# Pg04__AM335X_Section_3.net
KiCad netlist of a schematic drawn in Altium Designer
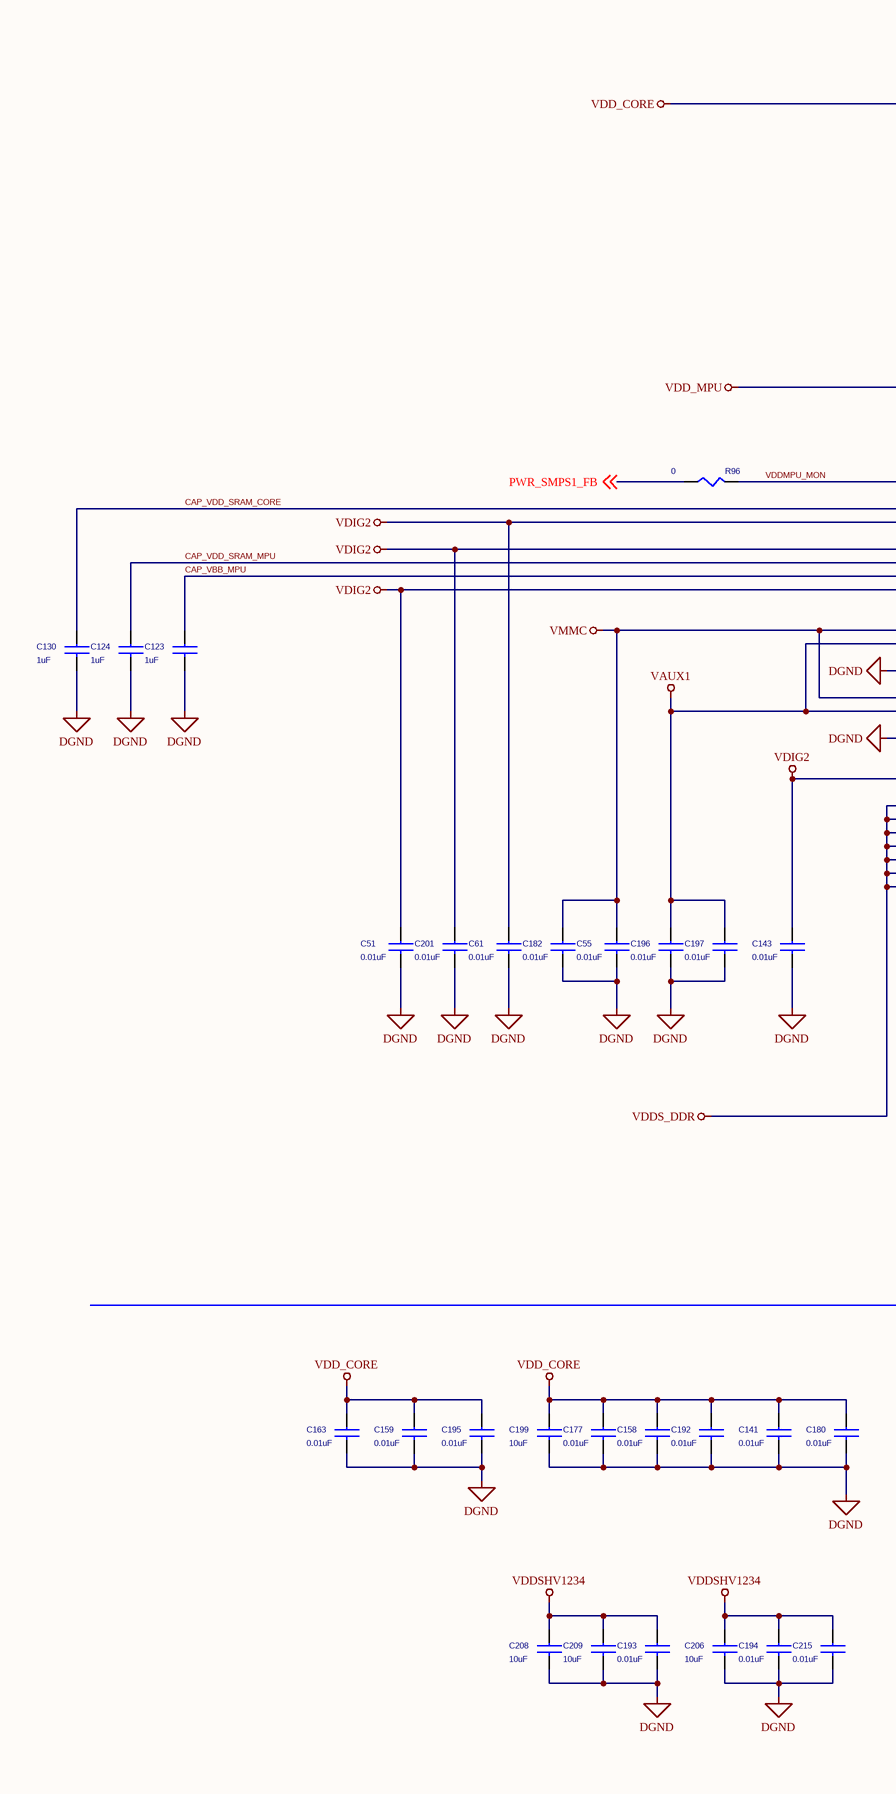
[diagram p0: Pg04_ AM335X Section 3 .SchDoc, left]
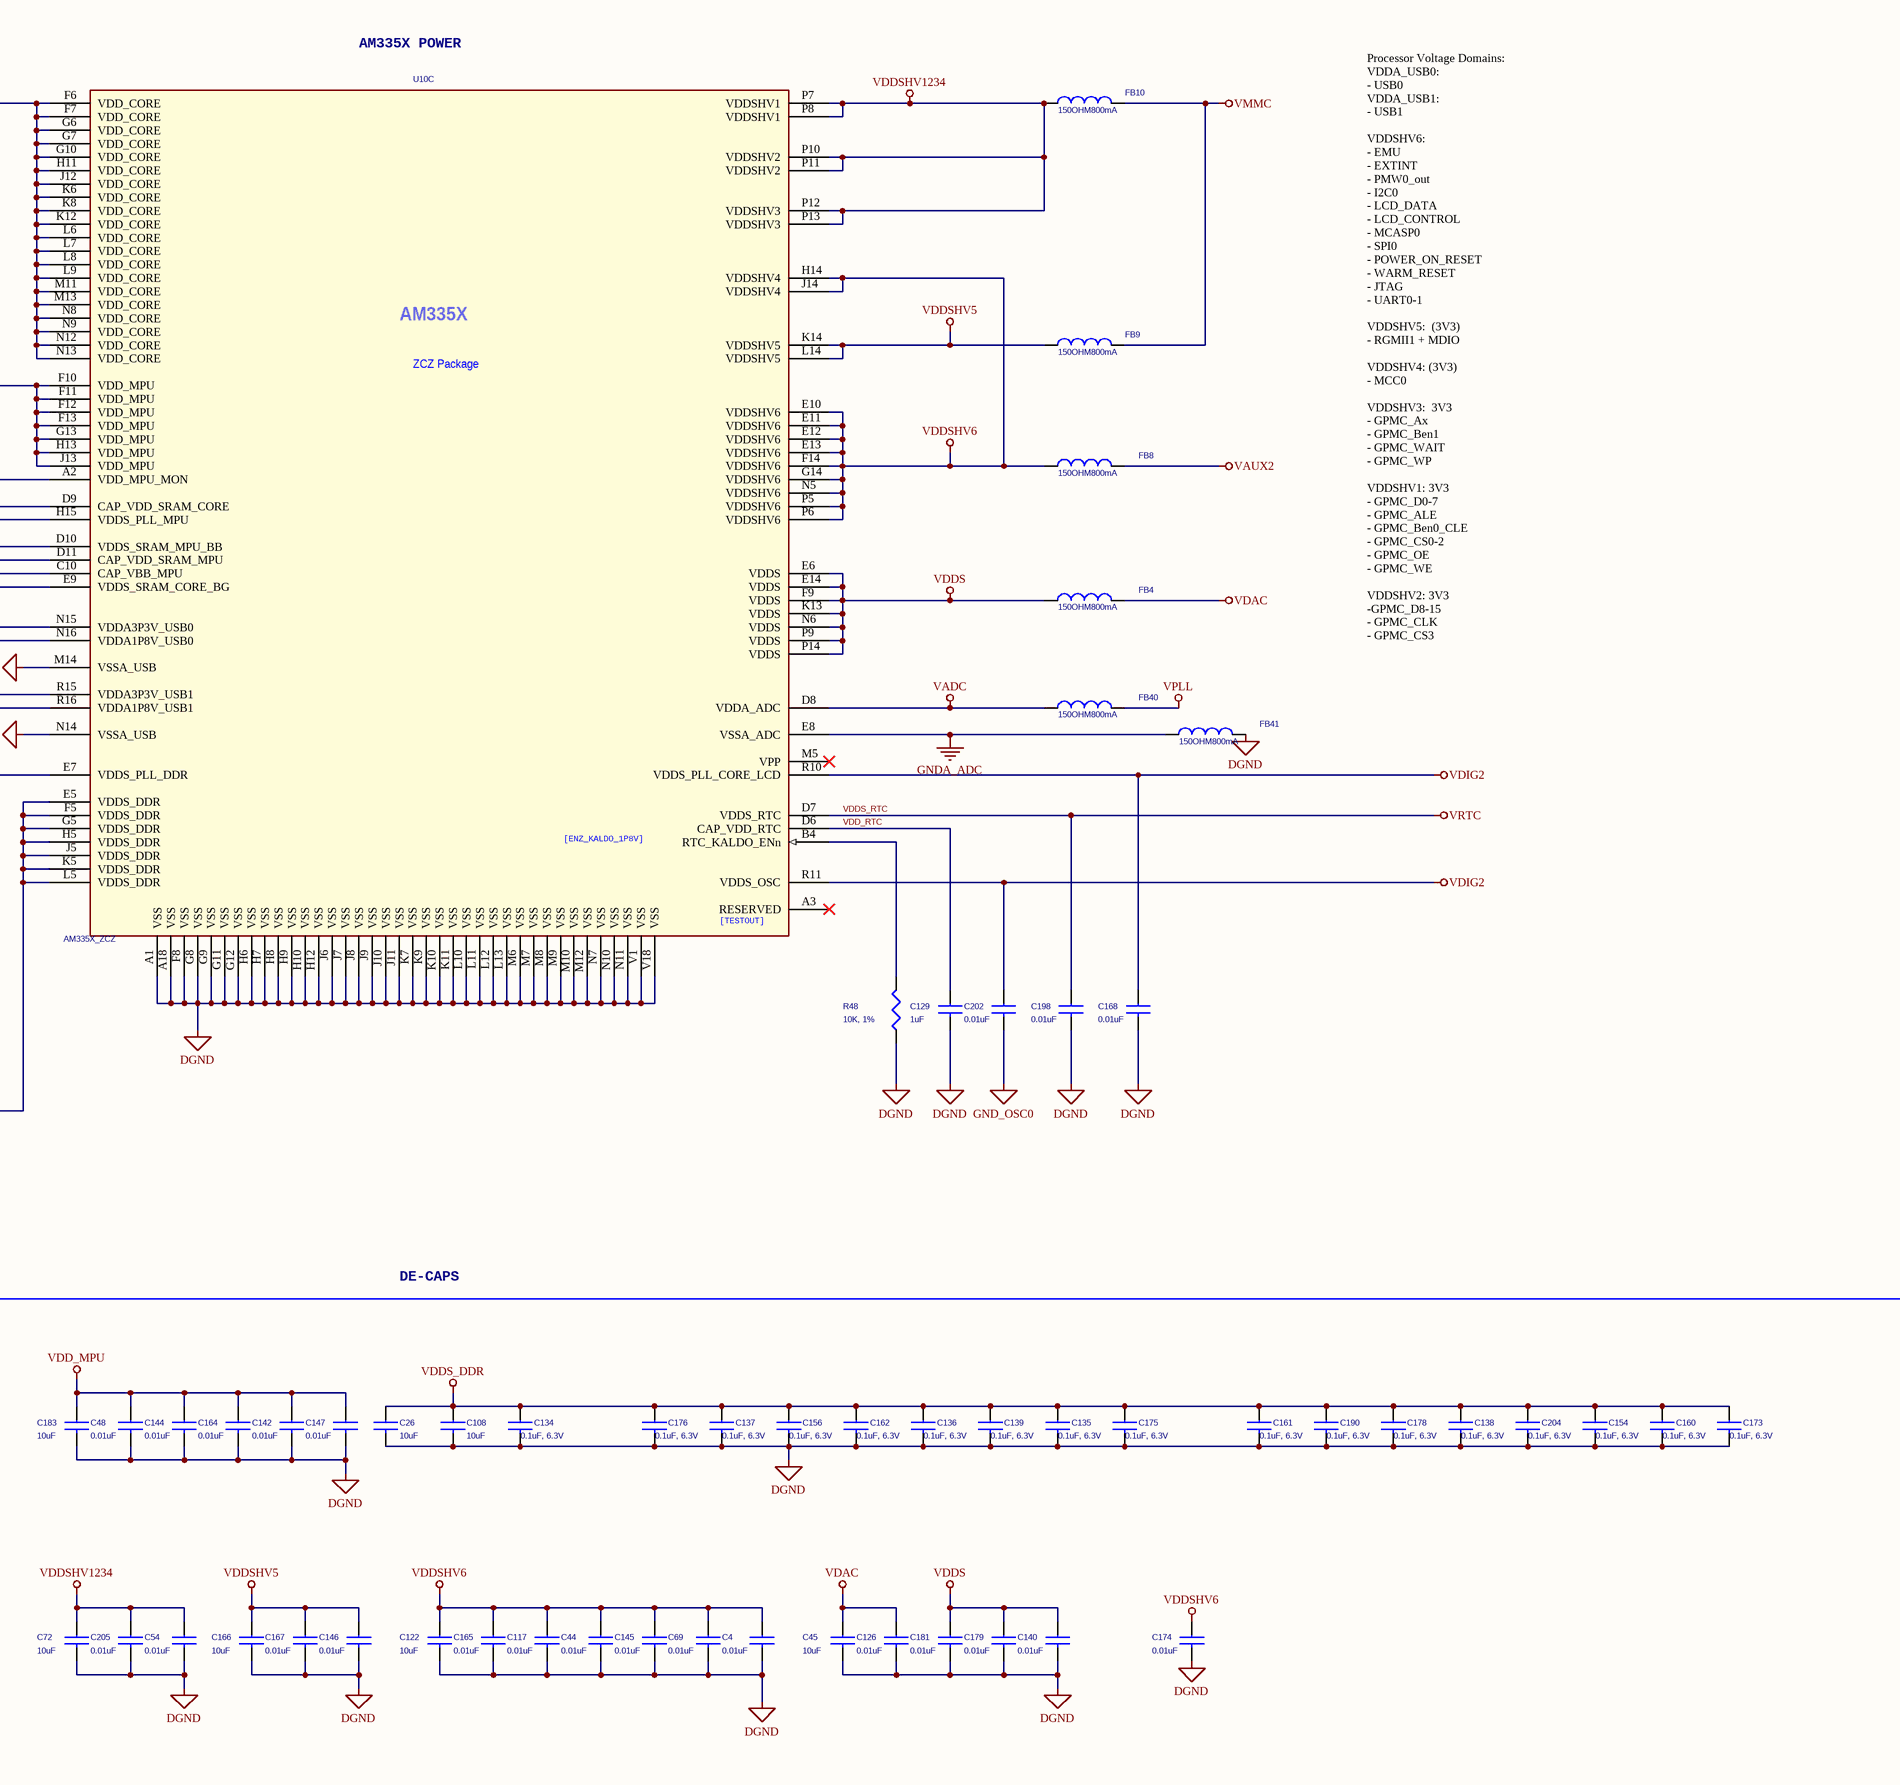
[diagram p1: Pg04_ AM335X Section 3 .SchDoc, right]

(export (version "E")
  (design (tool "Eeschema 10.0.6"))
  (components
    (comp (ref "C4")
      (value "0.01uF")
      (footprint "SM-7351-CAP-0402")
      (fields (field (name "MFR") "Panasonic") (field (name "TIINTPARTNUMBER") "1C0012"))
      (libsource (lib "*") (part "0.01uFCapacitor16V10%0402_Dup1"))
    )
    (comp (ref "C26")
      (value "10uF")
      (footprint "SM-7351-CAP-0805")
      (description "Capacitor 10uF 16V 10% Ceramic 0805")
      (fields (field (name "MFR") "AVX") (field (name "TIINTPARTNUMBER") "1C0085"))
      (libsource (lib "*") (part "10uFCapacitor16V10%0805"))
    )
    (comp (ref "C44")
      (value "0.01uF")
      (footprint "SM-7351-CAP-0402")
      (fields (field (name "MFR") "Panasonic") (field (name "TIINTPARTNUMBER") "1C0012"))
      (libsource (lib "*") (part "0.01uFCapacitor16V10%0402_Dup1"))
    )
    (comp (ref "C45")
      (value "10uF")
      (footprint "SM-7351-CAP-0805")
      (description "Capacitor 10uF 16V 10% Ceramic 0805")
      (fields (field (name "MFR") "AVX") (field (name "TIINTPARTNUMBER") "1C0085"))
      (libsource (lib "*") (part "10uFCapacitor16V10%0805"))
    )
    (comp (ref "C48")
      (value "0.01uF")
      (footprint "SM-7351-CAP-0402")
      (fields (field (name "MFR") "Panasonic") (field (name "TIINTPARTNUMBER") "1C0012"))
      (libsource (lib "*") (part "0.01uFCapacitor16V10%0402_Dup1"))
    )
    (comp (ref "C51")
      (value "0.01uF")
      (footprint "SM-7351-CAP-0402")
      (fields (field (name "MFR") "Panasonic") (field (name "TIINTPARTNUMBER") "1C0012"))
      (libsource (lib "*") (part "0.01uFCapacitor16V10%0402_Dup1"))
    )
    (comp (ref "C54")
      (value "0.01uF")
      (footprint "SM-7351-CAP-0402")
      (fields (field (name "MFR") "Panasonic") (field (name "TIINTPARTNUMBER") "1C0012"))
      (libsource (lib "*") (part "0.01uFCapacitor16V10%0402_Dup1"))
    )
    (comp (ref "C55")
      (value "0.01uF")
      (footprint "SM-7351-CAP-0402")
      (fields (field (name "MFR") "Panasonic") (field (name "TIINTPARTNUMBER") "1C0012"))
      (libsource (lib "*") (part "0.01uFCapacitor16V10%0402_Dup1"))
    )
    (comp (ref "C61")
      (value "0.01uF")
      (footprint "SM-7351-CAP-0402")
      (fields (field (name "MFR") "Panasonic") (field (name "TIINTPARTNUMBER") "1C0012"))
      (libsource (lib "*") (part "0.01uFCapacitor16V10%0402_Dup1"))
    )
    (comp (ref "C69")
      (value "0.01uF")
      (footprint "SM-7351-CAP-0402")
      (fields (field (name "MFR") "Panasonic") (field (name "TIINTPARTNUMBER") "1C0012"))
      (libsource (lib "*") (part "0.01uFCapacitor16V10%0402_Dup1"))
    )
    (comp (ref "C72")
      (value "10uF")
      (footprint "SM-7351-CAP-0805")
      (description "Capacitor 10uF 16V 10% Ceramic 0805")
      (fields (field (name "MFR") "AVX") (field (name "TIINTPARTNUMBER") "1C0085"))
      (libsource (lib "*") (part "10uFCapacitor16V10%0805"))
    )
    (comp (ref "C108")
      (value "10uF")
      (footprint "SM-7351-CAP-0805")
      (description "Capacitor 10uF 16V 10% Ceramic 0805")
      (fields (field (name "MFR") "AVX") (field (name "TIINTPARTNUMBER") "1C0085"))
      (libsource (lib "*") (part "10uFCapacitor16V10%0805"))
    )
    (comp (ref "C117")
      (value "0.01uF")
      (footprint "SM-7351-CAP-0402")
      (fields (field (name "MFR") "Panasonic") (field (name "TIINTPARTNUMBER") "1C0012"))
      (libsource (lib "*") (part "0.01uFCapacitor16V10%0402_Dup1"))
    )
    (comp (ref "C122")
      (value "10uF")
      (footprint "SM-7351-CAP-0805")
      (description "Capacitor 10uF 16V 10% Ceramic 0805")
      (fields (field (name "MFR") "AVX") (field (name "TIINTPARTNUMBER") "1C0085"))
      (libsource (lib "*") (part "10uFCapacitor16V10%0805"))
    )
    (comp (ref "C123")
      (value "1uF")
      (footprint "SM-7351-CAP-0402")
      (fields (field (name "MFR") "AVX") (field (name "TIINTPARTNUMBER") "1C0084"))
      (libsource (lib "*") (part "1uFCapacitor10V10%0402_Dup1"))
    )
    (comp (ref "C124")
      (value "1uF")
      (footprint "SM-7351-CAP-0402")
      (fields (field (name "MFR") "AVX") (field (name "TIINTPARTNUMBER") "1C0084"))
      (libsource (lib "*") (part "1uFCapacitor10V10%0402_Dup1"))
    )
    (comp (ref "C126")
      (value "0.01uF")
      (footprint "SM-7351-CAP-0402")
      (fields (field (name "MFR") "Panasonic") (field (name "TIINTPARTNUMBER") "1C0012"))
      (libsource (lib "*") (part "0.01uFCapacitor16V10%0402_Dup1"))
    )
    (comp (ref "C129")
      (value "1uF")
      (footprint "SM-7351-CAP-0402")
      (fields (field (name "MFR") "AVX") (field (name "TIINTPARTNUMBER") "1C0084"))
      (libsource (lib "*") (part "1uFCapacitor10V10%0402_Dup1"))
    )
    (comp (ref "C130")
      (value "1uF")
      (footprint "SM-7351-CAP-0402")
      (fields (field (name "MFR") "AVX") (field (name "TIINTPARTNUMBER") "1C0084"))
      (libsource (lib "*") (part "1uFCapacitor10V10%0402_Dup1"))
    )
    (comp (ref "C134")
      (value "0.1uF, 6.3V")
      (footprint "SM-7351-CAP-0402")
      (fields (field (name "MFR") "Murata") (field (name "TIINTPARTNUMBER") "1C0122"))
      (libsource (lib "*") (part "0.1uFCapacitor6.3V10%0201"))
    )
    (comp (ref "C135")
      (value "0.1uF, 6.3V")
      (footprint "SM-7351-CAP-0402")
      (fields (field (name "MFR") "Murata") (field (name "TIINTPARTNUMBER") "1C0122"))
      (libsource (lib "*") (part "0.1uFCapacitor6.3V10%0201"))
    )
    (comp (ref "C136")
      (value "0.1uF, 6.3V")
      (footprint "SM-7351-CAP-0402")
      (fields (field (name "MFR") "Murata") (field (name "TIINTPARTNUMBER") "1C0122"))
      (libsource (lib "*") (part "0.1uFCapacitor6.3V10%0201"))
    )
    (comp (ref "C137")
      (value "0.1uF, 6.3V")
      (footprint "SMD0201")
      (fields (field (name "MFR") "Murata") (field (name "TIINTPARTNUMBER") "1C0122"))
      (libsource (lib "*") (part "0.1uFCapacitor6.3V10%0201"))
    )
    (comp (ref "C138")
      (value "0.1uF, 6.3V")
      (footprint "SMD0201")
      (fields (field (name "MFR") "Murata") (field (name "TIINTPARTNUMBER") "1C0122"))
      (libsource (lib "*") (part "0.1uFCapacitor6.3V10%0201"))
    )
    (comp (ref "C139")
      (value "0.1uF, 6.3V")
      (footprint "SMD0201")
      (fields (field (name "MFR") "Murata") (field (name "TIINTPARTNUMBER") "1C0122"))
      (libsource (lib "*") (part "0.1uFCapacitor6.3V10%0201"))
    )
    (comp (ref "C140")
      (value "0.01uF")
      (footprint "SM-7351-CAP-0402")
      (fields (field (name "MFR") "Panasonic") (field (name "TIINTPARTNUMBER") "1C0012"))
      (libsource (lib "*") (part "0.01uFCapacitor16V10%0402_Dup1"))
    )
    (comp (ref "C141")
      (value "0.01uF")
      (footprint "SM-7351-CAP-0402")
      (fields (field (name "MFR") "Panasonic") (field (name "TIINTPARTNUMBER") "1C0012"))
      (libsource (lib "*") (part "0.01uFCapacitor16V10%0402_Dup1"))
    )
    (comp (ref "C142")
      (value "0.01uF")
      (footprint "SM-7351-CAP-0402")
      (fields (field (name "MFR") "Panasonic") (field (name "TIINTPARTNUMBER") "1C0012"))
      (libsource (lib "*") (part "0.01uFCapacitor16V10%0402_Dup1"))
    )
    (comp (ref "C143")
      (value "0.01uF")
      (footprint "SM-7351-CAP-0402")
      (fields (field (name "MFR") "Panasonic") (field (name "TIINTPARTNUMBER") "1C0012"))
      (libsource (lib "*") (part "0.01uFCapacitor16V10%0402_Dup1"))
    )
    (comp (ref "C144")
      (value "0.01uF")
      (footprint "SM-7351-CAP-0402")
      (fields (field (name "MFR") "Panasonic") (field (name "TIINTPARTNUMBER") "1C0012"))
      (libsource (lib "*") (part "0.01uFCapacitor16V10%0402_Dup1"))
    )
    (comp (ref "C145")
      (value "0.01uF")
      (footprint "SM-7351-CAP-0402")
      (fields (field (name "MFR") "Panasonic") (field (name "TIINTPARTNUMBER") "1C0012"))
      (libsource (lib "*") (part "0.01uFCapacitor16V10%0402_Dup1"))
    )
    (comp (ref "C146")
      (value "0.01uF")
      (footprint "SM-7351-CAP-0402")
      (fields (field (name "MFR") "Panasonic") (field (name "TIINTPARTNUMBER") "1C0012"))
      (libsource (lib "*") (part "0.01uFCapacitor16V10%0402_Dup1"))
    )
    (comp (ref "C147")
      (value "0.01uF")
      (footprint "SM-7351-CAP-0402")
      (fields (field (name "MFR") "Panasonic") (field (name "TIINTPARTNUMBER") "1C0012"))
      (libsource (lib "*") (part "0.01uFCapacitor16V10%0402_Dup1"))
    )
    (comp (ref "C154")
      (value "0.1uF, 6.3V")
      (footprint "SMD0201")
      (fields (field (name "MFR") "Murata") (field (name "TIINTPARTNUMBER") "1C0122"))
      (libsource (lib "*") (part "0.1uFCapacitor6.3V10%0201"))
    )
    (comp (ref "C156")
      (value "0.1uF, 6.3V")
      (footprint "SMD0201")
      (fields (field (name "MFR") "Murata") (field (name "TIINTPARTNUMBER") "1C0122"))
      (libsource (lib "*") (part "0.1uFCapacitor6.3V10%0201"))
    )
    (comp (ref "C158")
      (value "0.01uF")
      (footprint "SM-7351-CAP-0402")
      (fields (field (name "MFR") "Panasonic") (field (name "TIINTPARTNUMBER") "1C0012"))
      (libsource (lib "*") (part "0.01uFCapacitor16V10%0402_Dup1"))
    )
    (comp (ref "C159")
      (value "0.01uF")
      (footprint "SM-7351-CAP-0402")
      (fields (field (name "MFR") "Panasonic") (field (name "TIINTPARTNUMBER") "1C0012"))
      (libsource (lib "*") (part "0.01uFCapacitor16V10%0402_Dup1"))
    )
    (comp (ref "C160")
      (value "0.1uF, 6.3V")
      (footprint "SMD0201")
      (fields (field (name "MFR") "Murata") (field (name "TIINTPARTNUMBER") "1C0122"))
      (libsource (lib "*") (part "0.1uFCapacitor6.3V10%0201"))
    )
    (comp (ref "C161")
      (value "0.1uF, 6.3V")
      (footprint "SMD0201")
      (fields (field (name "MFR") "Murata") (field (name "TIINTPARTNUMBER") "1C0122"))
      (libsource (lib "*") (part "0.1uFCapacitor6.3V10%0201"))
    )
    (comp (ref "C162")
      (value "0.1uF, 6.3V")
      (footprint "SMD0201")
      (fields (field (name "MFR") "Murata") (field (name "TIINTPARTNUMBER") "1C0122"))
      (libsource (lib "*") (part "0.1uFCapacitor6.3V10%0201"))
    )
    (comp (ref "C163")
      (value "0.01uF")
      (footprint "SM-7351-CAP-0402")
      (fields (field (name "MFR") "Panasonic") (field (name "TIINTPARTNUMBER") "1C0012"))
      (libsource (lib "*") (part "0.01uFCapacitor16V10%0402_Dup1"))
    )
    (comp (ref "C164")
      (value "0.01uF")
      (footprint "SM-7351-CAP-0402")
      (fields (field (name "MFR") "Panasonic") (field (name "TIINTPARTNUMBER") "1C0012"))
      (libsource (lib "*") (part "0.01uFCapacitor16V10%0402_Dup1"))
    )
    (comp (ref "C165")
      (value "0.01uF")
      (footprint "SM-7351-CAP-0402")
      (fields (field (name "MFR") "Panasonic") (field (name "TIINTPARTNUMBER") "1C0012"))
      (libsource (lib "*") (part "0.01uFCapacitor16V10%0402_Dup1"))
    )
    (comp (ref "C166")
      (value "10uF")
      (footprint "SM-7351-CAP-0805")
      (description "Capacitor 10uF 16V 10% Ceramic 0805")
      (fields (field (name "MFR") "AVX") (field (name "TIINTPARTNUMBER") "1C0085"))
      (libsource (lib "*") (part "10uFCapacitor16V10%0805"))
    )
    (comp (ref "C167")
      (value "0.01uF")
      (footprint "SM-7351-CAP-0402")
      (fields (field (name "MFR") "Panasonic") (field (name "TIINTPARTNUMBER") "1C0012"))
      (libsource (lib "*") (part "0.01uFCapacitor16V10%0402_Dup1"))
    )
    (comp (ref "C168")
      (value "0.01uF")
      (footprint "SM-7351-CAP-0402")
      (fields (field (name "MFR") "Panasonic") (field (name "TIINTPARTNUMBER") "1C0012"))
      (libsource (lib "*") (part "0.01uFCapacitor16V10%0402_Dup1"))
    )
    (comp (ref "C173")
      (value "0.1uF, 6.3V")
      (footprint "SMD0201")
      (fields (field (name "MFR") "Murata") (field (name "TIINTPARTNUMBER") "1C0122"))
      (libsource (lib "*") (part "0.1uFCapacitor6.3V10%0201"))
    )
    (comp (ref "C174")
      (value "0.01uF")
      (footprint "SM-7351-CAP-0402")
      (fields (field (name "MFR") "Panasonic") (field (name "TIINTPARTNUMBER") "1C0012"))
      (libsource (lib "*") (part "0.01uFCapacitor16V10%0402_Dup1"))
    )
    (comp (ref "C175")
      (value "0.1uF, 6.3V")
      (footprint "SMD0201")
      (fields (field (name "MFR") "Murata") (field (name "TIINTPARTNUMBER") "1C0122"))
      (libsource (lib "*") (part "0.1uFCapacitor6.3V10%0201"))
    )
    (comp (ref "C176")
      (value "0.1uF, 6.3V")
      (footprint "SMD0201")
      (fields (field (name "MFR") "Murata") (field (name "TIINTPARTNUMBER") "1C0122"))
      (libsource (lib "*") (part "0.1uFCapacitor6.3V10%0201"))
    )
    (comp (ref "C177")
      (value "0.01uF")
      (footprint "SM-7351-CAP-0402")
      (fields (field (name "MFR") "Panasonic") (field (name "TIINTPARTNUMBER") "1C0012"))
      (libsource (lib "*") (part "0.01uFCapacitor16V10%0402_Dup1"))
    )
    (comp (ref "C178")
      (value "0.1uF, 6.3V")
      (footprint "SMD0201")
      (fields (field (name "MFR") "Murata") (field (name "TIINTPARTNUMBER") "1C0122"))
      (libsource (lib "*") (part "0.1uFCapacitor6.3V10%0201"))
    )
    (comp (ref "C179")
      (value "0.01uF")
      (footprint "SM-7351-CAP-0402")
      (fields (field (name "MFR") "Panasonic") (field (name "TIINTPARTNUMBER") "1C0012"))
      (libsource (lib "*") (part "0.01uFCapacitor16V10%0402_Dup1"))
    )
    (comp (ref "C180")
      (value "0.01uF")
      (footprint "SM-7351-CAP-0402")
      (fields (field (name "MFR") "Panasonic") (field (name "TIINTPARTNUMBER") "1C0012"))
      (libsource (lib "*") (part "0.01uFCapacitor16V10%0402_Dup1"))
    )
    (comp (ref "C181")
      (value "0.01uF")
      (footprint "SM-7351-CAP-0402")
      (fields (field (name "MFR") "Panasonic") (field (name "TIINTPARTNUMBER") "1C0012"))
      (libsource (lib "*") (part "0.01uFCapacitor16V10%0402_Dup1"))
    )
    (comp (ref "C182")
      (value "0.01uF")
      (footprint "SM-7351-CAP-0402")
      (fields (field (name "MFR") "Panasonic") (field (name "TIINTPARTNUMBER") "1C0012"))
      (libsource (lib "*") (part "0.01uFCapacitor16V10%0402_Dup1"))
    )
    (comp (ref "C183")
      (value "10uF")
      (footprint "SM-7351-CAP-0805")
      (description "Capacitor 10uF 16V 10% Ceramic 0805")
      (fields (field (name "MFR") "AVX") (field (name "TIINTPARTNUMBER") "1C0085"))
      (libsource (lib "*") (part "10uFCapacitor16V10%0805"))
    )
    (comp (ref "C190")
      (value "0.1uF, 6.3V")
      (footprint "SM-7351-CAP-0402")
      (fields (field (name "MFR") "Murata") (field (name "TIINTPARTNUMBER") "1C0122"))
      (libsource (lib "*") (part "0.1uFCapacitor6.3V10%0201"))
    )
    (comp (ref "C192")
      (value "0.01uF")
      (footprint "SM-7351-CAP-0402")
      (fields (field (name "MFR") "Panasonic") (field (name "TIINTPARTNUMBER") "1C0012"))
      (libsource (lib "*") (part "0.01uFCapacitor16V10%0402_Dup1"))
    )
    (comp (ref "C193")
      (value "0.01uF")
      (footprint "SM-7351-CAP-0402")
      (fields (field (name "MFR") "Panasonic") (field (name "TIINTPARTNUMBER") "1C0012"))
      (libsource (lib "*") (part "0.01uFCapacitor16V10%0402_Dup1"))
    )
    (comp (ref "C194")
      (value "0.01uF")
      (footprint "SM-7351-CAP-0402")
      (fields (field (name "MFR") "Panasonic") (field (name "TIINTPARTNUMBER") "1C0012"))
      (libsource (lib "*") (part "0.01uFCapacitor16V10%0402_Dup1"))
    )
    (comp (ref "C195")
      (value "0.01uF")
      (footprint "SM-7351-CAP-0402")
      (fields (field (name "MFR") "Panasonic") (field (name "TIINTPARTNUMBER") "1C0012"))
      (libsource (lib "*") (part "0.01uFCapacitor16V10%0402_Dup1"))
    )
    (comp (ref "C196")
      (value "0.01uF")
      (footprint "SM-7351-CAP-0402")
      (fields (field (name "MFR") "Panasonic") (field (name "TIINTPARTNUMBER") "1C0012"))
      (libsource (lib "*") (part "0.01uFCapacitor16V10%0402_Dup1"))
    )
    (comp (ref "C197")
      (value "0.01uF")
      (footprint "SM-7351-CAP-0402")
      (fields (field (name "MFR") "Panasonic") (field (name "TIINTPARTNUMBER") "1C0012"))
      (libsource (lib "*") (part "0.01uFCapacitor16V10%0402_Dup1"))
    )
    (comp (ref "C198")
      (value "0.01uF")
      (footprint "SM-7351-CAP-0402")
      (fields (field (name "MFR") "Panasonic") (field (name "TIINTPARTNUMBER") "1C0012"))
      (libsource (lib "*") (part "0.01uFCapacitor16V10%0402_Dup1"))
    )
    (comp (ref "C199")
      (value "10uF")
      (footprint "SM-7351-CAP-0805")
      (description "Capacitor 10uF 16V 10% Ceramic 0805")
      (fields (field (name "MFR") "AVX") (field (name "TIINTPARTNUMBER") "1C0085"))
      (libsource (lib "*") (part "10uFCapacitor16V10%0805"))
    )
    (comp (ref "C201")
      (value "0.01uF")
      (footprint "SM-7351-CAP-0402")
      (fields (field (name "MFR") "Panasonic") (field (name "TIINTPARTNUMBER") "1C0012"))
      (libsource (lib "*") (part "0.01uFCapacitor16V10%0402_Dup1"))
    )
    (comp (ref "C202")
      (value "0.01uF")
      (footprint "SM-7351-CAP-0402")
      (fields (field (name "MFR") "Panasonic") (field (name "TIINTPARTNUMBER") "1C0012"))
      (libsource (lib "*") (part "0.01uFCapacitor16V10%0402_Dup1"))
    )
    (comp (ref "C204")
      (value "0.1uF, 6.3V")
      (footprint "SM-7351-CAP-0402")
      (fields (field (name "MFR") "Murata") (field (name "TIINTPARTNUMBER") "1C0122"))
      (libsource (lib "*") (part "0.1uFCapacitor6.3V10%0201"))
    )
    (comp (ref "C205")
      (value "0.01uF")
      (footprint "SM-7351-CAP-0402")
      (fields (field (name "MFR") "Panasonic") (field (name "TIINTPARTNUMBER") "1C0012"))
      (libsource (lib "*") (part "0.01uFCapacitor16V10%0402_Dup1"))
    )
    (comp (ref "C206")
      (value "10uF")
      (footprint "SM-7351-CAP-0805")
      (description "Capacitor 10uF 16V 10% Ceramic 0805")
      (fields (field (name "MFR") "AVX") (field (name "TIINTPARTNUMBER") "1C0085"))
      (libsource (lib "*") (part "10uFCapacitor16V10%0805"))
    )
    (comp (ref "C208")
      (value "10uF")
      (footprint "SM-7351-CAP-0805")
      (description "Capacitor 10uF 16V 10% Ceramic 0805")
      (fields (field (name "MFR") "AVX") (field (name "TIINTPARTNUMBER") "1C0085"))
      (libsource (lib "*") (part "10uFCapacitor16V10%0805"))
    )
    (comp (ref "C209")
      (value "10uF")
      (footprint "SM-7351-CAP-0805")
      (description "Capacitor 10uF 16V 10% Ceramic 0805")
      (fields (field (name "MFR") "AVX") (field (name "TIINTPARTNUMBER") "1C0085"))
      (libsource (lib "*") (part "10uFCapacitor16V10%0805"))
    )
    (comp (ref "C215")
      (value "0.01uF")
      (footprint "SM-7351-CAP-0402")
      (fields (field (name "MFR") "Panasonic") (field (name "TIINTPARTNUMBER") "1C0012"))
      (libsource (lib "*") (part "0.01uFCapacitor16V10%0402_Dup1"))
    )
    (comp (ref "FB4")
      (value "150OHM800mA")
      (footprint "sm-7351-ind-0805")
      (description "Ferrite Bead 150 Ohm 800mA")
      (fields (field (name "MFR") "Steward") (field (name "TIINTPARTNUMBER") "1L0010"))
      (libsource (lib "*") (part "FerBead_12"))
    )
    (comp (ref "FB8")
      (value "150OHM800mA")
      (footprint "sm-7351-ind-0805")
      (description "Ferrite Bead 150 Ohm 800mA")
      (fields (field (name "MFR") "Steward") (field (name "TIINTPARTNUMBER") "1L0010"))
      (libsource (lib "*") (part "FerBead_12"))
    )
    (comp (ref "FB9")
      (value "150OHM800mA")
      (footprint "sm-7351-ind-0805")
      (description "Ferrite Bead 150 Ohm 800mA")
      (fields (field (name "MFR") "Steward") (field (name "TIINTPARTNUMBER") "1L0010"))
      (libsource (lib "*") (part "FerBead_11"))
    )
    (comp (ref "FB10")
      (value "150OHM800mA")
      (footprint "sm-7351-ind-0805")
      (description "Ferrite Bead 150 Ohm 800mA")
      (fields (field (name "MFR") "Steward") (field (name "TIINTPARTNUMBER") "1L0010"))
      (libsource (lib "*") (part "FerBead_7"))
    )
    (comp (ref "FB40")
      (value "150OHM800mA")
      (footprint "sm-7351-ind-0805")
      (description "Ferrite Bead 150 Ohm 800mA")
      (fields (field (name "MFR") "Steward") (field (name "TIINTPARTNUMBER") "1L0010"))
      (libsource (lib "*") (part "FerBead_12"))
    )
    (comp (ref "FB41")
      (value "150OHM800mA")
      (footprint "sm-7351-ind-0805")
      (description "Ferrite Bead 150 Ohm 800mA")
      (fields (field (name "MFR") "Steward") (field (name "TIINTPARTNUMBER") "1L0010"))
      (libsource (lib "*") (part "FerBead_12"))
    )
    (comp (ref "R48")
      (value "10K, 1%")
      (footprint "SM-7351-RES-0402")
      (fields (field (name "TIINTPARTNUMBER") "1R0254") (field (name "MFR") "PANASONIC-ECG"))
      (libsource (lib "*") (part "10KOhmResistor1/10W1%0402_Dup2"))
    )
    (comp (ref "R96")
      (value "0")
      (footprint "SM-7351-RES-0402")
      (description "Resistor Zero ohm Jumper 0402")
      (fields (field (name "TIINTPARTNUMBER") "1R0098") (field (name "MFR") "Panasonic"))
      (libsource (lib "*") (part "ZeroOhmResistor1/16W0402_Dup4"))
    )
    (comp (ref "U10")
      (value "AM335X_ZCZ")
      (footprint "BGA15X15-324-55M")
      (fields (field (name "TIINTPARTNUMBER") "1A0242") (field (name "MFR") "TI"))
      (libsource (lib "*") (part "AM335X_15mmx15mm"))
    )
  )
  (nets
    (net (code "1") (name "/CAP_VBB_MPU") (class "Default")
      (node (ref "C123") (pin "1") (pinfunction "1_1") (pintype "passive"))
      (node (ref "U10") (pin "C10") (pinfunction "CAP_VBB_MPU_C10") (pintype "passive"))
    )
    (net (code "2") (name "/CAP_VDD_SRAM_CORE") (class "Default")
      (node (ref "C130") (pin "1") (pinfunction "1_1") (pintype "passive"))
      (node (ref "U10") (pin "D9") (pinfunction "CAP_VDD_SRAM_CORE_D9") (pintype "power_in"))
    )
    (net (code "3") (name "/CAP_VDD_SRAM_MPU") (class "Default")
      (node (ref "C124") (pin "1") (pinfunction "1_1") (pintype "passive"))
      (node (ref "U10") (pin "D11") (pinfunction "CAP_VDD_SRAM_MPU_D11") (pintype "power_in"))
    )
    (net (code "4") (name "/VDDMPU_MON") (class "Default")
      (node (ref "R96") (pin "1") (pinfunction "P1_1") (pintype "passive"))
      (node (ref "U10") (pin "A2") (pinfunction "VDD_MPU_MON_A2") (pintype "passive"))
    )
    (net (code "5") (name "/VDD_RTC") (class "Default")
      (node (ref "C129") (pin "1") (pinfunction "1_1") (pintype "passive"))
      (node (ref "U10") (pin "D6") (pinfunction "CAP_VDD_RTC_D6") (pintype "power_in"))
    )
    (net (code "6") (name "DGND") (class "Default")
      (node (ref "C108") (pin "2") (pinfunction "2_2") (pintype "passive"))
      (node (ref "C117") (pin "2") (pinfunction "2_2") (pintype "passive"))
      (node (ref "C122") (pin "2") (pinfunction "2_2") (pintype "passive"))
      (node (ref "C123") (pin "2") (pinfunction "2_2") (pintype "passive"))
      (node (ref "C124") (pin "2") (pinfunction "2_2") (pintype "passive"))
      (node (ref "C126") (pin "2") (pinfunction "2_2") (pintype "passive"))
      (node (ref "C129") (pin "2") (pinfunction "2_2") (pintype "passive"))
      (node (ref "C130") (pin "2") (pinfunction "2_2") (pintype "passive"))
      (node (ref "C134") (pin "2") (pinfunction "2_2") (pintype "passive"))
      (node (ref "C135") (pin "2") (pinfunction "2_2") (pintype "passive"))
      (node (ref "C136") (pin "2") (pinfunction "2_2") (pintype "passive"))
      (node (ref "C137") (pin "2") (pinfunction "2_2") (pintype "passive"))
      (node (ref "C138") (pin "2") (pinfunction "2_2") (pintype "passive"))
      (node (ref "C139") (pin "2") (pinfunction "2_2") (pintype "passive"))
      (node (ref "C140") (pin "2") (pinfunction "2_2") (pintype "passive"))
      (node (ref "C141") (pin "2") (pinfunction "2_2") (pintype "passive"))
      (node (ref "C142") (pin "2") (pinfunction "2_2") (pintype "passive"))
      (node (ref "C143") (pin "2") (pinfunction "2_2") (pintype "passive"))
      (node (ref "C144") (pin "2") (pinfunction "2_2") (pintype "passive"))
      (node (ref "C145") (pin "2") (pinfunction "2_2") (pintype "passive"))
      (node (ref "C146") (pin "2") (pinfunction "2_2") (pintype "passive"))
      (node (ref "C147") (pin "2") (pinfunction "2_2") (pintype "passive"))
      (node (ref "C154") (pin "2") (pinfunction "2_2") (pintype "passive"))
      (node (ref "C156") (pin "2") (pinfunction "2_2") (pintype "passive"))
      (node (ref "C158") (pin "2") (pinfunction "2_2") (pintype "passive"))
      (node (ref "C159") (pin "2") (pinfunction "2_2") (pintype "passive"))
      (node (ref "C160") (pin "2") (pinfunction "2_2") (pintype "passive"))
      (node (ref "C161") (pin "2") (pinfunction "2_2") (pintype "passive"))
      (node (ref "C162") (pin "2") (pinfunction "2_2") (pintype "passive"))
      (node (ref "C163") (pin "2") (pinfunction "2_2") (pintype "passive"))
      (node (ref "C164") (pin "2") (pinfunction "2_2") (pintype "passive"))
      (node (ref "C165") (pin "2") (pinfunction "2_2") (pintype "passive"))
      (node (ref "C166") (pin "2") (pinfunction "2_2") (pintype "passive"))
      (node (ref "C167") (pin "2") (pinfunction "2_2") (pintype "passive"))
      (node (ref "C168") (pin "2") (pinfunction "2_2") (pintype "passive"))
      (node (ref "C173") (pin "2") (pinfunction "2_2") (pintype "passive"))
      (node (ref "C174") (pin "2") (pinfunction "2_2") (pintype "passive"))
      (node (ref "C175") (pin "2") (pinfunction "2_2") (pintype "passive"))
      (node (ref "C176") (pin "2") (pinfunction "2_2") (pintype "passive"))
      (node (ref "C177") (pin "2") (pinfunction "2_2") (pintype "passive"))
      (node (ref "C178") (pin "2") (pinfunction "2_2") (pintype "passive"))
      (node (ref "C179") (pin "2") (pinfunction "2_2") (pintype "passive"))
      (node (ref "C180") (pin "2") (pinfunction "2_2") (pintype "passive"))
      (node (ref "C181") (pin "2") (pinfunction "2_2") (pintype "passive"))
      (node (ref "C182") (pin "2") (pinfunction "2_2") (pintype "passive"))
      (node (ref "C183") (pin "2") (pinfunction "2_2") (pintype "passive"))
      (node (ref "C190") (pin "2") (pinfunction "2_2") (pintype "passive"))
      (node (ref "C192") (pin "2") (pinfunction "2_2") (pintype "passive"))
      (node (ref "C193") (pin "2") (pinfunction "2_2") (pintype "passive"))
      (node (ref "C194") (pin "2") (pinfunction "2_2") (pintype "passive"))
      (node (ref "C195") (pin "2") (pinfunction "2_2") (pintype "passive"))
      (node (ref "C196") (pin "2") (pinfunction "2_2") (pintype "passive"))
      (node (ref "C197") (pin "2") (pinfunction "2_2") (pintype "passive"))
      (node (ref "C198") (pin "2") (pinfunction "2_2") (pintype "passive"))
      (node (ref "C199") (pin "2") (pinfunction "2_2") (pintype "passive"))
      (node (ref "C201") (pin "2") (pinfunction "2_2") (pintype "passive"))
      (node (ref "C204") (pin "2") (pinfunction "2_2") (pintype "passive"))
      (node (ref "C205") (pin "2") (pinfunction "2_2") (pintype "passive"))
      (node (ref "C206") (pin "2") (pinfunction "2_2") (pintype "passive"))
      (node (ref "C208") (pin "2") (pinfunction "2_2") (pintype "passive"))
      (node (ref "C209") (pin "2") (pinfunction "2_2") (pintype "passive"))
      (node (ref "C215") (pin "2") (pinfunction "2_2") (pintype "passive"))
      (node (ref "C26") (pin "2") (pinfunction "2_2") (pintype "passive"))
      (node (ref "C4") (pin "2") (pinfunction "2_2") (pintype "passive"))
      (node (ref "C44") (pin "2") (pinfunction "2_2") (pintype "passive"))
      (node (ref "C45") (pin "2") (pinfunction "2_2") (pintype "passive"))
      (node (ref "C48") (pin "2") (pinfunction "2_2") (pintype "passive"))
      (node (ref "C51") (pin "2") (pinfunction "2_2") (pintype "passive"))
      (node (ref "C54") (pin "2") (pinfunction "2_2") (pintype "passive"))
      (node (ref "C55") (pin "2") (pinfunction "2_2") (pintype "passive"))
      (node (ref "C61") (pin "2") (pinfunction "2_2") (pintype "passive"))
      (node (ref "C69") (pin "2") (pinfunction "2_2") (pintype "passive"))
      (node (ref "C72") (pin "2") (pinfunction "2_2") (pintype "passive"))
      (node (ref "FB41") (pin "2") (pinfunction "2_2") (pintype "passive"))
      (node (ref "R48") (pin "1") (pinfunction "1_1") (pintype "passive"))
      (node (ref "U10") (pin "A1") (pinfunction "VSS_A1") (pintype "power_in"))
      (node (ref "U10") (pin "A18") (pinfunction "VSS_A18") (pintype "power_in"))
      (node (ref "U10") (pin "F8") (pinfunction "VSS_F8") (pintype "power_in"))
      (node (ref "U10") (pin "G11") (pinfunction "VSS_G11") (pintype "power_in"))
      (node (ref "U10") (pin "G12") (pinfunction "VSS_G12") (pintype "power_in"))
      (node (ref "U10") (pin "G8") (pinfunction "VSS_G8") (pintype "power_in"))
      (node (ref "U10") (pin "G9") (pinfunction "VSS_G9") (pintype "power_in"))
      (node (ref "U10") (pin "H10") (pinfunction "VSS_H10") (pintype "power_in"))
      (node (ref "U10") (pin "H12") (pinfunction "VSS_H12") (pintype "power_in"))
      (node (ref "U10") (pin "H6") (pinfunction "VSS_H6") (pintype "power_in"))
      (node (ref "U10") (pin "H7") (pinfunction "VSS_H7") (pintype "power_in"))
      (node (ref "U10") (pin "H8") (pinfunction "VSS_H8") (pintype "power_in"))
      (node (ref "U10") (pin "H9") (pinfunction "VSS_H9") (pintype "power_in"))
      (node (ref "U10") (pin "J10") (pinfunction "VSS_J10") (pintype "power_in"))
      (node (ref "U10") (pin "J11") (pinfunction "VSS_J11") (pintype "power_in"))
      (node (ref "U10") (pin "J6") (pinfunction "VSS_J6") (pintype "power_in"))
      (node (ref "U10") (pin "J7") (pinfunction "VSS_J7") (pintype "power_in"))
      (node (ref "U10") (pin "J8") (pinfunction "VSS_J8") (pintype "power_in"))
      (node (ref "U10") (pin "J9") (pinfunction "VSS_J9") (pintype "power_in"))
      (node (ref "U10") (pin "K10") (pinfunction "VSS_K10") (pintype "power_in"))
      (node (ref "U10") (pin "K11") (pinfunction "VSS_K11") (pintype "power_in"))
      (node (ref "U10") (pin "K7") (pinfunction "VSS_K7") (pintype "power_in"))
      (node (ref "U10") (pin "K9") (pinfunction "VSS_K9") (pintype "power_in"))
      (node (ref "U10") (pin "L10") (pinfunction "VSS_L10") (pintype "power_in"))
      (node (ref "U10") (pin "L11") (pinfunction "VSS_L11") (pintype "power_in"))
      (node (ref "U10") (pin "L12") (pinfunction "VSS_L12") (pintype "power_in"))
      (node (ref "U10") (pin "L13") (pinfunction "VSS_L13") (pintype "power_in"))
      (node (ref "U10") (pin "M10") (pinfunction "VSS_M10") (pintype "power_in"))
      (node (ref "U10") (pin "M12") (pinfunction "VSS_M12") (pintype "power_in"))
      (node (ref "U10") (pin "M14") (pinfunction "VSSA_USB_M14") (pintype "power_in"))
      (node (ref "U10") (pin "M6") (pinfunction "VSS_M6") (pintype "power_in"))
      (node (ref "U10") (pin "M7") (pinfunction "VSS_M7") (pintype "power_in"))
      (node (ref "U10") (pin "M8") (pinfunction "VSS_M8") (pintype "power_in"))
      (node (ref "U10") (pin "M9") (pinfunction "VSS_M9") (pintype "power_in"))
      (node (ref "U10") (pin "N10") (pinfunction "VSS_N10") (pintype "power_in"))
      (node (ref "U10") (pin "N11") (pinfunction "VSS_N11") (pintype "power_in"))
      (node (ref "U10") (pin "N14") (pinfunction "VSSA_USB_N14") (pintype "power_in"))
      (node (ref "U10") (pin "N7") (pinfunction "VSS_N7") (pintype "power_in"))
      (node (ref "U10") (pin "V1") (pinfunction "VSS_V1") (pintype "power_in"))
      (node (ref "U10") (pin "V18") (pinfunction "VSS_V18") (pintype "power_in"))
    )
    (net (code "7") (name "GNDA_ADC") (class "Default")
      (node (ref "FB41") (pin "1") (pinfunction "1_1") (pintype "passive"))
      (node (ref "U10") (pin "E8") (pinfunction "VSSA_ADC_E8") (pintype "power_in"))
    )
    (net (code "8") (name "GND_OSC0") (class "Default")
      (node (ref "C202") (pin "2") (pinfunction "2_2") (pintype "passive"))
    )
    (net (code "9") (name "Net-(U10C-RTC_KALDO_ENn)") (class "Default")
      (node (ref "R48") (pin "2") (pinfunction "2_2") (pintype "passive"))
      (node (ref "U10") (pin "B4") (pinfunction "RTC_KALDO_ENn_B4") (pintype "input"))
    )
    (net (code "10") (name "PWR_SMPS1_FB") (class "Default")
      (node (ref "R96") (pin "2") (pinfunction "P2_2") (pintype "passive"))
    )
    (net (code "11") (name "VADC") (class "Default")
      (node (ref "FB40") (pin "1") (pinfunction "1_1") (pintype "passive"))
      (node (ref "U10") (pin "D8") (pinfunction "VDDA_ADC_D8") (pintype "power_in"))
    )
    (net (code "12") (name "VAUX1") (class "Default")
      (node (ref "C196") (pin "1") (pinfunction "1_1") (pintype "passive"))
      (node (ref "C197") (pin "1") (pinfunction "1_1") (pintype "passive"))
      (node (ref "U10") (pin "N16") (pinfunction "VDDA1P8V_USB0_N16") (pintype "power_in"))
      (node (ref "U10") (pin "R16") (pinfunction "VDDA1P8V_USB1_R16") (pintype "power_in"))
    )
    (net (code "13") (name "VAUX2") (class "Default")
      (node (ref "FB8") (pin "2") (pinfunction "2_2") (pintype "passive"))
    )
    (net (code "14") (name "VDAC") (class "Default")
      (node (ref "C126") (pin "1") (pinfunction "1_1") (pintype "passive"))
      (node (ref "C45") (pin "1") (pinfunction "1_1") (pintype "passive"))
      (node (ref "FB4") (pin "2") (pinfunction "2_2") (pintype "passive"))
    )
    (net (code "15") (name "VDDS") (class "Default")
      (node (ref "C140") (pin "1") (pinfunction "1_1") (pintype "passive"))
      (node (ref "C179") (pin "1") (pinfunction "1_1") (pintype "passive"))
      (node (ref "C181") (pin "1") (pinfunction "1_1") (pintype "passive"))
      (node (ref "FB4") (pin "1") (pinfunction "1_1") (pintype "passive"))
      (node (ref "U10") (pin "E14") (pinfunction "VDDS_E14") (pintype "power_in"))
      (node (ref "U10") (pin "E6") (pinfunction "VDDS_E6") (pintype "power_in"))
      (node (ref "U10") (pin "F9") (pinfunction "VDDS_F9") (pintype "power_in"))
      (node (ref "U10") (pin "K13") (pinfunction "VDDS_K13") (pintype "power_in"))
      (node (ref "U10") (pin "N6") (pinfunction "VDDS_N6") (pintype "power_in"))
      (node (ref "U10") (pin "P14") (pinfunction "VDDS_P14") (pintype "power_in"))
      (node (ref "U10") (pin "P9") (pinfunction "VDDS_P9") (pintype "power_in"))
    )
    (net (code "16") (name "VDDSHV5") (class "Default")
      (node (ref "C146") (pin "1") (pinfunction "1_1") (pintype "passive"))
      (node (ref "C166") (pin "1") (pinfunction "1_1") (pintype "passive"))
      (node (ref "C167") (pin "1") (pinfunction "1_1") (pintype "passive"))
      (node (ref "FB9") (pin "1") (pinfunction "1_1") (pintype "passive"))
      (node (ref "U10") (pin "K14") (pinfunction "VDDSHV5_K14") (pintype "power_in"))
      (node (ref "U10") (pin "L14") (pinfunction "VDDSHV5_L14") (pintype "power_in"))
    )
    (net (code "17") (name "VDDSHV6") (class "Default")
      (node (ref "C117") (pin "1") (pinfunction "1_1") (pintype "passive"))
      (node (ref "C122") (pin "1") (pinfunction "1_1") (pintype "passive"))
      (node (ref "C145") (pin "1") (pinfunction "1_1") (pintype "passive"))
      (node (ref "C165") (pin "1") (pinfunction "1_1") (pintype "passive"))
      (node (ref "C174") (pin "1") (pinfunction "1_1") (pintype "passive"))
      (node (ref "C4") (pin "1") (pinfunction "1_1") (pintype "passive"))
      (node (ref "C44") (pin "1") (pinfunction "1_1") (pintype "passive"))
      (node (ref "C69") (pin "1") (pinfunction "1_1") (pintype "passive"))
      (node (ref "FB8") (pin "1") (pinfunction "1_1") (pintype "passive"))
      (node (ref "U10") (pin "E10") (pinfunction "VDDSHV6_E10") (pintype "power_in"))
      (node (ref "U10") (pin "E11") (pinfunction "VDDSHV6_E11") (pintype "power_in"))
      (node (ref "U10") (pin "E12") (pinfunction "VDDSHV6_E12") (pintype "power_in"))
      (node (ref "U10") (pin "E13") (pinfunction "VDDSHV6_E13") (pintype "power_in"))
      (node (ref "U10") (pin "F14") (pinfunction "VDDSHV6_F14") (pintype "power_in"))
      (node (ref "U10") (pin "G14") (pinfunction "VDDSHV6_G14") (pintype "power_in"))
      (node (ref "U10") (pin "H14") (pinfunction "VDDSHV4_H14") (pintype "power_in"))
      (node (ref "U10") (pin "J14") (pinfunction "VDDSHV4_J14") (pintype "power_in"))
      (node (ref "U10") (pin "N5") (pinfunction "VDDSHV6_N5") (pintype "power_in"))
      (node (ref "U10") (pin "P5") (pinfunction "VDDSHV6_P5") (pintype "power_in"))
      (node (ref "U10") (pin "P6") (pinfunction "VDDSHV6_P6") (pintype "power_in"))
    )
    (net (code "18") (name "VDDSHV1234") (class "Default")
      (node (ref "C193") (pin "1") (pinfunction "1_1") (pintype "passive"))
      (node (ref "C194") (pin "1") (pinfunction "1_1") (pintype "passive"))
      (node (ref "C205") (pin "1") (pinfunction "1_1") (pintype "passive"))
      (node (ref "C206") (pin "1") (pinfunction "1_1") (pintype "passive"))
      (node (ref "C208") (pin "1") (pinfunction "1_1") (pintype "passive"))
      (node (ref "C209") (pin "1") (pinfunction "1_1") (pintype "passive"))
      (node (ref "C215") (pin "1") (pinfunction "1_1") (pintype "passive"))
      (node (ref "C54") (pin "1") (pinfunction "1_1") (pintype "passive"))
      (node (ref "C72") (pin "1") (pinfunction "1_1") (pintype "passive"))
      (node (ref "FB10") (pin "1") (pinfunction "1_1") (pintype "passive"))
      (node (ref "U10") (pin "P10") (pinfunction "VDDSHV2_P10") (pintype "power_in"))
      (node (ref "U10") (pin "P11") (pinfunction "VDDSHV2_P11") (pintype "power_in"))
      (node (ref "U10") (pin "P12") (pinfunction "VDDSHV3_P12") (pintype "power_in"))
      (node (ref "U10") (pin "P13") (pinfunction "VDDSHV3_P13") (pintype "power_in"))
      (node (ref "U10") (pin "P7") (pinfunction "VDDSHV1_P7") (pintype "power_in"))
      (node (ref "U10") (pin "P8") (pinfunction "VDDSHV1_P8") (pintype "power_in"))
    )
    (net (code "19") (name "VDDS_DDR") (class "Default")
      (node (ref "C108") (pin "1") (pinfunction "1_1") (pintype "passive"))
      (node (ref "C134") (pin "1") (pinfunction "1_1") (pintype "passive"))
      (node (ref "C135") (pin "1") (pinfunction "1_1") (pintype "passive"))
      (node (ref "C136") (pin "1") (pinfunction "1_1") (pintype "passive"))
      (node (ref "C137") (pin "1") (pinfunction "1_1") (pintype "passive"))
      (node (ref "C138") (pin "1") (pinfunction "1_1") (pintype "passive"))
      (node (ref "C139") (pin "1") (pinfunction "1_1") (pintype "passive"))
      (node (ref "C154") (pin "1") (pinfunction "1_1") (pintype "passive"))
      (node (ref "C156") (pin "1") (pinfunction "1_1") (pintype "passive"))
      (node (ref "C160") (pin "1") (pinfunction "1_1") (pintype "passive"))
      (node (ref "C161") (pin "1") (pinfunction "1_1") (pintype "passive"))
      (node (ref "C162") (pin "1") (pinfunction "1_1") (pintype "passive"))
      (node (ref "C173") (pin "1") (pinfunction "1_1") (pintype "passive"))
      (node (ref "C175") (pin "1") (pinfunction "1_1") (pintype "passive"))
      (node (ref "C176") (pin "1") (pinfunction "1_1") (pintype "passive"))
      (node (ref "C178") (pin "1") (pinfunction "1_1") (pintype "passive"))
      (node (ref "C190") (pin "1") (pinfunction "1_1") (pintype "passive"))
      (node (ref "C204") (pin "1") (pinfunction "1_1") (pintype "passive"))
      (node (ref "C26") (pin "1") (pinfunction "1_1") (pintype "passive"))
      (node (ref "U10") (pin "E5") (pinfunction "VDDS_DDR_E5") (pintype "power_in"))
      (node (ref "U10") (pin "F5") (pinfunction "VDDS_DDR_F5") (pintype "power_in"))
      (node (ref "U10") (pin "G5") (pinfunction "VDDS_DDR_G5") (pintype "power_in"))
      (node (ref "U10") (pin "H5") (pinfunction "VDDS_DDR_H5") (pintype "power_in"))
      (node (ref "U10") (pin "J5") (pinfunction "VDDS_DDR_J5") (pintype "power_in"))
      (node (ref "U10") (pin "K5") (pinfunction "VDDS_DDR_K5") (pintype "power_in"))
      (node (ref "U10") (pin "L5") (pinfunction "VDDS_DDR_L5") (pintype "power_in"))
    )
    (net (code "20") (name "VDD_CORE") (class "Default")
      (node (ref "C141") (pin "1") (pinfunction "1_1") (pintype "passive"))
      (node (ref "C158") (pin "1") (pinfunction "1_1") (pintype "passive"))
      (node (ref "C159") (pin "1") (pinfunction "1_1") (pintype "passive"))
      (node (ref "C163") (pin "1") (pinfunction "1_1") (pintype "passive"))
      (node (ref "C177") (pin "1") (pinfunction "1_1") (pintype "passive"))
      (node (ref "C180") (pin "1") (pinfunction "1_1") (pintype "passive"))
      (node (ref "C192") (pin "1") (pinfunction "1_1") (pintype "passive"))
      (node (ref "C195") (pin "1") (pinfunction "1_1") (pintype "passive"))
      (node (ref "C199") (pin "1") (pinfunction "1_1") (pintype "passive"))
      (node (ref "U10") (pin "F6") (pinfunction "VDD_CORE_F6") (pintype "power_in"))
      (node (ref "U10") (pin "F7") (pinfunction "VDD_CORE_F7") (pintype "power_in"))
      (node (ref "U10") (pin "G10") (pinfunction "VDD_CORE_G10") (pintype "power_in"))
      (node (ref "U10") (pin "G6") (pinfunction "VDD_CORE_G6") (pintype "power_in"))
      (node (ref "U10") (pin "G7") (pinfunction "VDD_CORE_G7") (pintype "power_in"))
      (node (ref "U10") (pin "H11") (pinfunction "VDD_CORE_H11") (pintype "power_in"))
      (node (ref "U10") (pin "J12") (pinfunction "VDD_CORE_J12") (pintype "power_in"))
      (node (ref "U10") (pin "K12") (pinfunction "VDD_CORE_K12") (pintype "power_in"))
      (node (ref "U10") (pin "K6") (pinfunction "VDD_CORE_K6") (pintype "power_in"))
      (node (ref "U10") (pin "K8") (pinfunction "VDD_CORE_K8") (pintype "power_in"))
      (node (ref "U10") (pin "L6") (pinfunction "VDD_CORE_L6") (pintype "power_in"))
      (node (ref "U10") (pin "L7") (pinfunction "VDD_CORE_L7") (pintype "power_in"))
      (node (ref "U10") (pin "L8") (pinfunction "VDD_CORE_L8") (pintype "power_in"))
      (node (ref "U10") (pin "L9") (pinfunction "VDD_CORE_L9") (pintype "power_in"))
      (node (ref "U10") (pin "M11") (pinfunction "VDD_CORE_M11") (pintype "power_in"))
      (node (ref "U10") (pin "M13") (pinfunction "VDD_CORE_M13") (pintype "power_in"))
      (node (ref "U10") (pin "N12") (pinfunction "VDD_CORE_N12") (pintype "power_in"))
      (node (ref "U10") (pin "N13") (pinfunction "VDD_CORE_N13") (pintype "power_in"))
      (node (ref "U10") (pin "N8") (pinfunction "VDD_CORE_N8") (pintype "power_in"))
      (node (ref "U10") (pin "N9") (pinfunction "VDD_CORE_N9") (pintype "power_in"))
    )
    (net (code "21") (name "VDD_MPU") (class "Default")
      (node (ref "C142") (pin "1") (pinfunction "1_1") (pintype "passive"))
      (node (ref "C144") (pin "1") (pinfunction "1_1") (pintype "passive"))
      (node (ref "C147") (pin "1") (pinfunction "1_1") (pintype "passive"))
      (node (ref "C164") (pin "1") (pinfunction "1_1") (pintype "passive"))
      (node (ref "C183") (pin "1") (pinfunction "1_1") (pintype "passive"))
      (node (ref "C48") (pin "1") (pinfunction "1_1") (pintype "passive"))
      (node (ref "U10") (pin "F10") (pinfunction "VDD_MPU_F10") (pintype "power_in"))
      (node (ref "U10") (pin "F11") (pinfunction "VDD_MPU_F11") (pintype "power_in"))
      (node (ref "U10") (pin "F12") (pinfunction "VDD_MPU_F12") (pintype "power_in"))
      (node (ref "U10") (pin "F13") (pinfunction "VDD_MPU_F13") (pintype "power_in"))
      (node (ref "U10") (pin "G13") (pinfunction "VDD_MPU_G13") (pintype "power_in"))
      (node (ref "U10") (pin "H13") (pinfunction "VDD_MPU_H13") (pintype "power_in"))
      (node (ref "U10") (pin "J13") (pinfunction "VDD_MPU_J13") (pintype "power_in"))
    )
    (net (code "22") (name "VDIG2") (class "Default")
      (node (ref "C143") (pin "1") (pinfunction "1_1") (pintype "passive"))
      (node (ref "C168") (pin "1") (pinfunction "1_1") (pintype "passive"))
      (node (ref "C201") (pin "1") (pinfunction "1_1") (pintype "passive"))
      (node (ref "C202") (pin "1") (pinfunction "1_1") (pintype "passive"))
      (node (ref "C51") (pin "1") (pinfunction "1_1") (pintype "passive"))
      (node (ref "C61") (pin "1") (pinfunction "1_1") (pintype "passive"))
      (node (ref "U10") (pin "D10") (pinfunction "VDDS_SRAM_MPU_BB_D10") (pintype "power_in"))
      (node (ref "U10") (pin "E7") (pinfunction "VDDS_PLL_DDR_E7") (pintype "power_in"))
      (node (ref "U10") (pin "E9") (pinfunction "VDDS_SRAM_CORE_BG_E9") (pintype "power_in"))
      (node (ref "U10") (pin "H15") (pinfunction "VDDS_PLL_MPU_H15") (pintype "power_in"))
      (node (ref "U10") (pin "R10") (pinfunction "VDDS_PLL_CORE_LCD_R10") (pintype "power_in"))
      (node (ref "U10") (pin "R11") (pinfunction "VDDS_OSC_R11") (pintype "power_in"))
    )
    (net (code "23") (name "VMMC") (class "Default")
      (node (ref "C182") (pin "1") (pinfunction "1_1") (pintype "passive"))
      (node (ref "C55") (pin "1") (pinfunction "1_1") (pintype "passive"))
      (node (ref "FB10") (pin "2") (pinfunction "2_2") (pintype "passive"))
      (node (ref "FB9") (pin "2") (pinfunction "2_2") (pintype "passive"))
      (node (ref "U10") (pin "N15") (pinfunction "VDDA3P3V_USB0_N15") (pintype "power_in"))
      (node (ref "U10") (pin "R15") (pinfunction "VDDA3P3V_USB1_R15") (pintype "power_in"))
    )
    (net (code "24") (name "VPLL") (class "Default")
      (node (ref "FB40") (pin "2") (pinfunction "2_2") (pintype "passive"))
    )
    (net (code "25") (name "VRTC") (class "Default")
      (node (ref "C198") (pin "1") (pinfunction "1_1") (pintype "passive"))
      (node (ref "U10") (pin "D7") (pinfunction "VDDS_RTC_D7") (pintype "power_in"))
    )
    (net (code "26") (name "unconnected-(U10C-RESERVED-PadA3)") (class "Default")
      (node (ref "U10") (pin "A3") (pinfunction "RESERVED_A3") (pintype "passive+no_connect"))
    )
    (net (code "27") (name "unconnected-(U10C-VPP-PadM5)") (class "Default")
      (node (ref "U10") (pin "M5") (pinfunction "VPP_M5") (pintype "power_in+no_connect"))
    )
  )
)
